# MSP430v2.net
KiCad netlist of a schematic drawn in Altium Designer
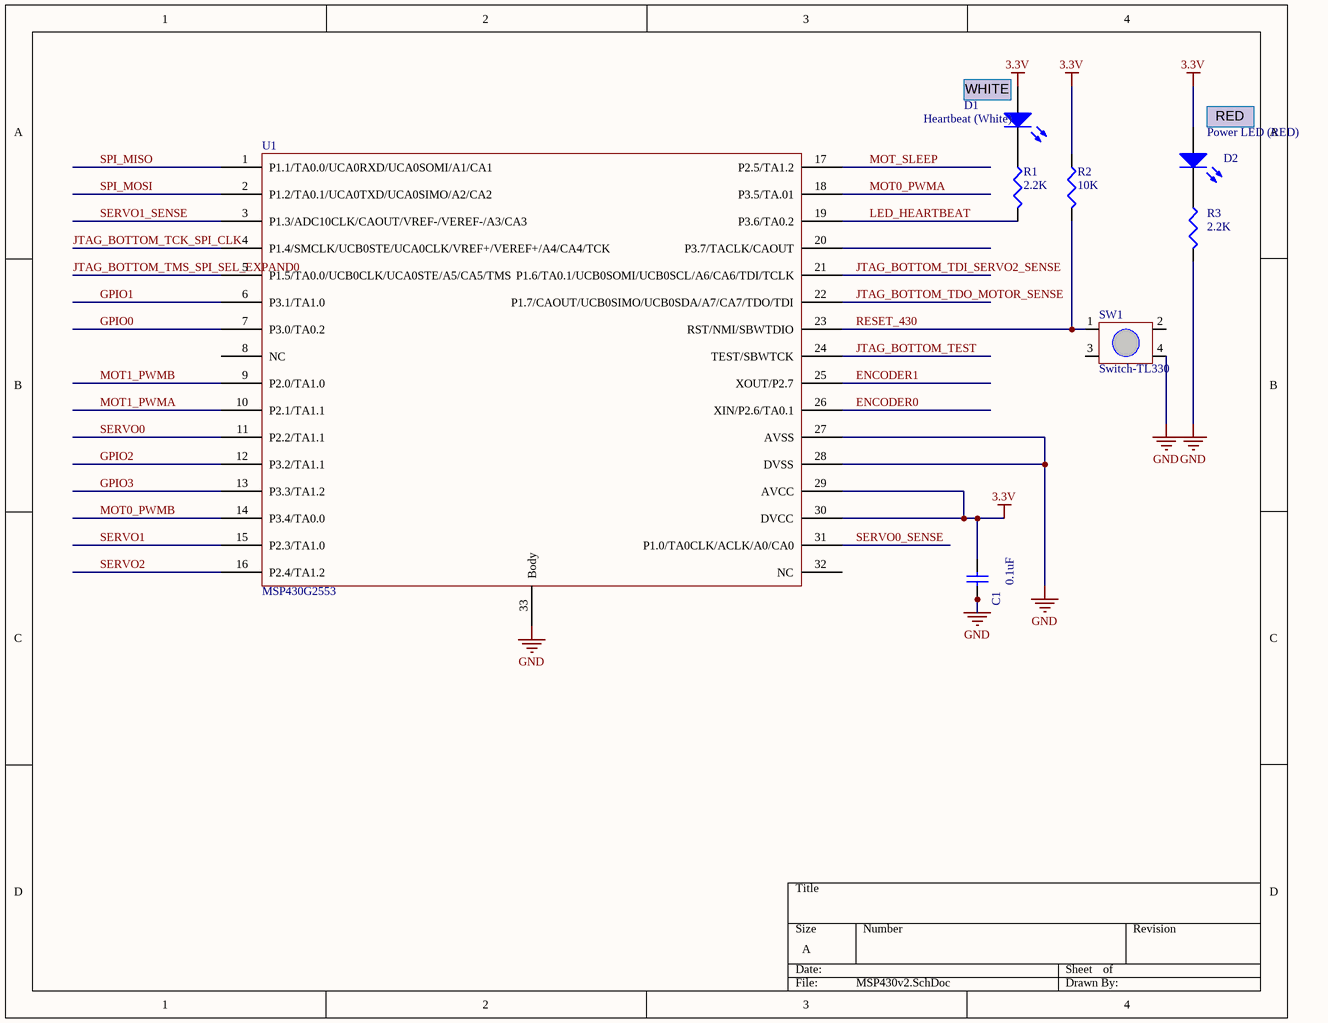
[diagram p0: MSP430v2.SchDoc]

(export (version "E")
  (design (tool "Eeschema 10.0.6"))
  (components
    (comp (ref "C1")
      (value "0.1uF")
      (footprint "CAPC1005L")
      (description "Capacitor (Semiconductor SIM Model)")
      (fields (field (name "Comment") "Cap Semi") (field (name "PUBLISHER") "Altium Limited"))
      (libsource (lib "Miscellaneous Devices") (part "Cap Semi"))
    )
    (comp (ref "D1")
      (value "Heartbeat (White)")
      (footprint "SurfaceMount(603)")
      (libsource (lib "mrone") (part "LED"))
    )
    (comp (ref "D2")
      (value "Power LED (RED)")
      (footprint "SurfaceMount(603)")
      (libsource (lib "mrone") (part "LED"))
    )
    (comp (ref "R1")
      (value "2.2K")
      (footprint "J1-0603")
      (description "Resistor")
      (fields (field (name "Comment") "DiodeRes") (field (name "PUBLISHER") "Altium Limited"))
      (libsource (lib "Miscellaneous Devices") (part "Res3"))
    )
    (comp (ref "R2")
      (value "10K")
      (footprint "J1-0603")
      (description "Resistor")
      (fields (field (name "Comment") "ResetRes") (field (name "PUBLISHER") "Altium Limited"))
      (libsource (lib "Miscellaneous Devices") (part "Res3"))
    )
    (comp (ref "R3")
      (value "2.2K")
      (footprint "J1-0603")
      (description "Resistor")
      (fields (field (name "Comment") "DiodeRes") (field (name "PUBLISHER") "Altium Limited"))
      (libsource (lib "Miscellaneous Devices") (part "Res3"))
    )
    (comp (ref "SW1")
      (value "Switch-TL330")
      (footprint "SwitchTall-TL330")
      (libsource (lib "mrone") (part "Switch-TL330"))
    )
    (comp (ref "U1")
      (value "MSP430G2553")
      (footprint "QFN-32")
      (libsource (lib "mrone") (part "MSP430G2553"))
    )
  )
  (nets
    (net (code "1") (name "/ENCODER0") (class "Default")
      (node (ref "U1") (pin "26") (pinfunction "XIN/P2.6/TA0.1_26") (pintype "passive"))
    )
    (net (code "2") (name "/ENCODER1") (class "Default")
      (node (ref "U1") (pin "25") (pinfunction "XOUT/P2.7_25") (pintype "passive"))
    )
    (net (code "3") (name "/GPIO0") (class "Default")
      (node (ref "U1") (pin "7") (pinfunction "P3.0/TA0.2_7") (pintype "passive"))
    )
    (net (code "4") (name "/GPIO1") (class "Default")
      (node (ref "U1") (pin "6") (pinfunction "P3.1/TA1.0_6") (pintype "passive"))
    )
    (net (code "5") (name "/GPIO2") (class "Default")
      (node (ref "U1") (pin "12") (pinfunction "P3.2/TA1.1_12") (pintype "passive"))
    )
    (net (code "6") (name "/GPIO3") (class "Default")
      (node (ref "U1") (pin "13") (pinfunction "P3.3/TA1.2_13") (pintype "passive"))
    )
    (net (code "7") (name "/JTAG_BOTTOM_TCK_SPI_CLK") (class "Default")
      (node (ref "U1") (pin "4") (pinfunction "P1.4/SMCLK/UCB0STE/UCA0CLK/VREF+/VEREF+/A4/CA4/TCK_4") (pintype "passive"))
    )
    (net (code "8") (name "/JTAG_BOTTOM_TDI_SERVO2_SENSE") (class "Default")
      (node (ref "U1") (pin "21") (pinfunction "P1.6/TA0.1/UCB0SOMI/UCB0SCL/A6/CA6/TDI/TCLK_21") (pintype "passive"))
    )
    (net (code "9") (name "/JTAG_BOTTOM_TDO_MOTOR_SENSE") (class "Default")
      (node (ref "U1") (pin "22") (pinfunction "P1.7/CAOUT/UCB0SIMO/UCB0SDA/A7/CA7/TDO/TDI_22") (pintype "passive"))
    )
    (net (code "10") (name "/JTAG_BOTTOM_TEST") (class "Default")
      (node (ref "U1") (pin "24") (pinfunction "TEST/SBWTCK_24") (pintype "passive"))
    )
    (net (code "11") (name "/JTAG_BOTTOM_TMS_SPI_SEL_EXPAND0") (class "Default")
      (node (ref "U1") (pin "5") (pinfunction "P1.5/TA0.0/UCB0CLK/UCA0STE/A5/CA5/TMS_5") (pintype "passive"))
    )
    (net (code "12") (name "/LED_HEARTBEAT") (class "Default")
      (node (ref "R1") (pin "2") (pinfunction "2_2") (pintype "passive"))
      (node (ref "U1") (pin "19") (pinfunction "P3.6/TA0.2_19") (pintype "passive"))
    )
    (net (code "13") (name "/MOT0_PWMA") (class "Default")
      (node (ref "U1") (pin "18") (pinfunction "P3.5/TA.01_18") (pintype "passive"))
    )
    (net (code "14") (name "/MOT0_PWMB") (class "Default")
      (node (ref "U1") (pin "14") (pinfunction "P3.4/TA0.0_14") (pintype "passive"))
    )
    (net (code "15") (name "/MOT1_PWMA") (class "Default")
      (node (ref "U1") (pin "10") (pinfunction "P2.1/TA1.1_10") (pintype "passive"))
    )
    (net (code "16") (name "/MOT1_PWMB") (class "Default")
      (node (ref "U1") (pin "9") (pinfunction "P2.0/TA1.0_9") (pintype "passive"))
    )
    (net (code "17") (name "/MOT_SLEEP") (class "Default")
      (node (ref "U1") (pin "17") (pinfunction "P2.5/TA1.2_17") (pintype "passive"))
    )
    (net (code "18") (name "/RESET_430") (class "Default")
      (node (ref "R2") (pin "2") (pinfunction "2_2") (pintype "passive"))
      (node (ref "SW1") (pin "1") (pinfunction "1_1") (pintype "passive"))
      (node (ref "U1") (pin "23") (pinfunction "RST/NMI/SBWTDIO_23") (pintype "passive"))
    )
    (net (code "19") (name "/SERVO0") (class "Default")
      (node (ref "U1") (pin "11") (pinfunction "P2.2/TA1.1_11") (pintype "passive"))
    )
    (net (code "20") (name "/SERVO0_SENSE") (class "Default")
      (node (ref "U1") (pin "31") (pinfunction "P1.0/TA0CLK/ACLK/A0/CA0_31") (pintype "passive"))
    )
    (net (code "21") (name "/SERVO1") (class "Default")
      (node (ref "U1") (pin "15") (pinfunction "P2.3/TA1.0_15") (pintype "passive"))
    )
    (net (code "22") (name "/SERVO1_SENSE") (class "Default")
      (node (ref "U1") (pin "3") (pinfunction "P1.3/ADC10CLK/CAOUT/VREF-/VEREF-/A3/CA3_3") (pintype "passive"))
    )
    (net (code "23") (name "/SERVO2") (class "Default")
      (node (ref "U1") (pin "16") (pinfunction "P2.4/TA1.2_16") (pintype "passive"))
    )
    (net (code "24") (name "/SPI_MISO") (class "Default")
      (node (ref "U1") (pin "1") (pinfunction "P1.1/TA0.0/UCA0RXD/UCA0SOMI/A1/CA1_1") (pintype "passive"))
    )
    (net (code "25") (name "/SPI_MOSI") (class "Default")
      (node (ref "U1") (pin "2") (pinfunction "P1.2/TA0.1/UCA0TXD/UCA0SIMO/A2/CA2_2") (pintype "passive"))
    )
    (net (code "26") (name "3.3V") (class "Default")
      (node (ref "C1") (pin "2") (pinfunction "2_2") (pintype "passive"))
      (node (ref "D1") (pin "1") (pinfunction "A_1") (pintype "passive"))
      (node (ref "D2") (pin "1") (pinfunction "A_1") (pintype "passive"))
      (node (ref "R2") (pin "1") (pinfunction "1_1") (pintype "passive"))
      (node (ref "U1") (pin "29") (pinfunction "AVCC_29") (pintype "passive"))
      (node (ref "U1") (pin "30") (pinfunction "DVCC_30") (pintype "passive"))
    )
    (net (code "27") (name "GND") (class "Default")
      (node (ref "C1") (pin "1") (pinfunction "1_1") (pintype "passive"))
      (node (ref "R3") (pin "2") (pinfunction "2_2") (pintype "passive"))
      (node (ref "SW1") (pin "4") (pinfunction "4_4") (pintype "passive"))
      (node (ref "U1") (pin "27") (pinfunction "AVSS_27") (pintype "passive"))
      (node (ref "U1") (pin "28") (pinfunction "DVSS_28") (pintype "passive"))
      (node (ref "U1") (pin "33") (pinfunction "Body_33") (pintype "passive"))
    )
    (net (code "28") (name "Net-(D1-K)") (class "Default")
      (node (ref "D1") (pin "2") (pinfunction "K_2") (pintype "passive"))
      (node (ref "R1") (pin "1") (pinfunction "1_1") (pintype "passive"))
    )
    (net (code "29") (name "Net-(D2-K)") (class "Default")
      (node (ref "D2") (pin "2") (pinfunction "K_2") (pintype "passive"))
      (node (ref "R3") (pin "1") (pinfunction "1_1") (pintype "passive"))
    )
    (net (code "30") (name "unconnected-(SW1-Pad2)") (class "Default")
      (node (ref "SW1") (pin "2") (pinfunction "2_2") (pintype "passive"))
    )
    (net (code "31") (name "unconnected-(SW1-Pad3)") (class "Default")
      (node (ref "SW1") (pin "3") (pinfunction "3_3") (pintype "passive"))
    )
    (net (code "32") (name "unconnected-(U1-NC-Pad8)") (class "Default")
      (node (ref "U1") (pin "8") (pinfunction "NC_8") (pintype "passive"))
    )
    (net (code "33") (name "unconnected-(U1-NC-Pad32)") (class "Default")
      (node (ref "U1") (pin "32") (pinfunction "NC_32") (pintype "passive"))
    )
    (net (code "34") (name "unconnected-(U1-P3.7{slash}TACLK{slash}CAOUT-Pad20)") (class "Default")
      (node (ref "U1") (pin "20") (pinfunction "P3.7/TACLK/CAOUT_20") (pintype "passive"))
    )
  )
)
